# frog.net
KiCad netlist of a schematic drawn in EAGLE
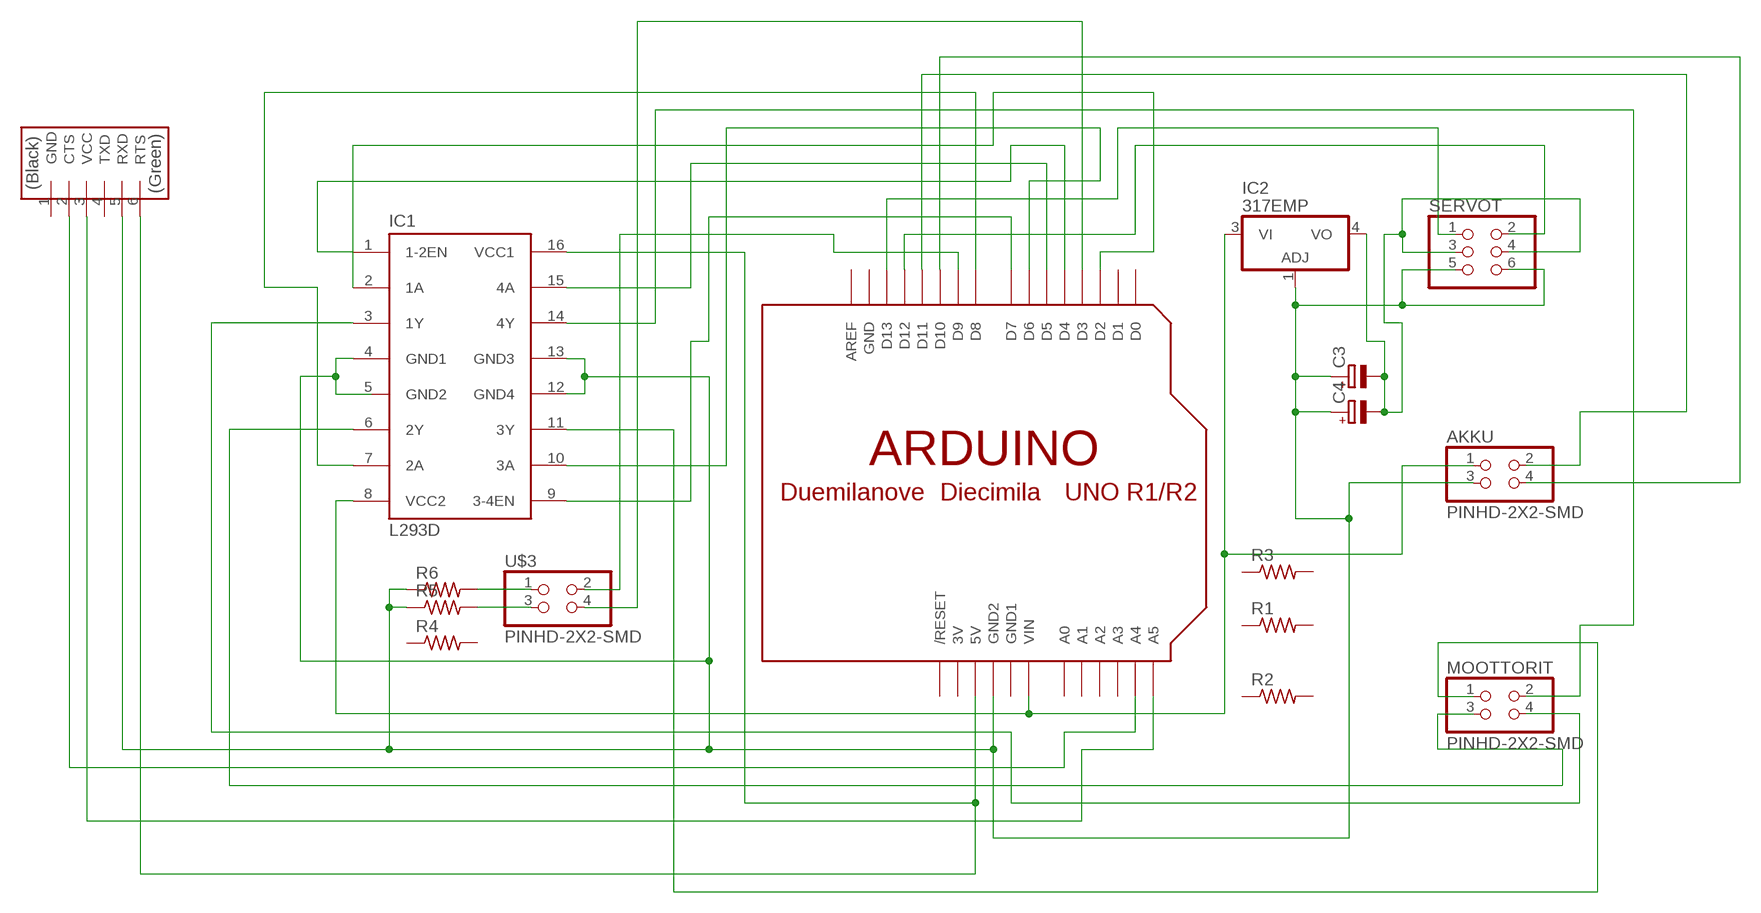
[diagram p0: schematic, sheet 1]

(export (version "E")
  (design (tool "Eeschema 10.0.6"))
  (components
    (comp (ref "AKKU")
      (value "PINHD-2X2-SMD")
      (footprint "eagle-import:2X02SMD")
      (libsource (lib "eagle-import") (part "PINHD-2X2-SMD"))
    )
    (comp (ref "C3")
      (value "CPOL-EUE/7260-38W")
      (footprint "eagle-import:E_7260-38W")
      (libsource (lib "eagle-import") (part "CPOL-EUE/7260-38W"))
    )
    (comp (ref "C4")
      (value "CPOL-EUE/7260-38W")
      (footprint "eagle-import:E_7260-38W")
      (libsource (lib "eagle-import") (part "CPOL-EUE/7260-38W"))
    )
    (comp (ref "IC1")
      (value "L293D")
      (footprint "eagle-import:DIL16")
      (libsource (lib "eagle-import") (part "L293D"))
    )
    (comp (ref "IC2")
      (value "317EMP")
      (footprint "eagle-import:SOT223")
      (libsource (lib "eagle-import") (part "317EMP"))
    )
    (comp (ref "MOOTTORIT")
      (value "PINHD-2X2-SMD")
      (footprint "eagle-import:2X02SMD")
      (libsource (lib "eagle-import") (part "PINHD-2X2-SMD"))
    )
    (comp (ref "R1")
      (value "RES-US1206FAB")
      (footprint "eagle-import:R1206FAB")
      (libsource (lib "eagle-import") (part "RES-US1206FAB"))
    )
    (comp (ref "R2")
      (value "RES-US1206FAB")
      (footprint "eagle-import:R1206FAB")
      (libsource (lib "eagle-import") (part "RES-US1206FAB"))
    )
    (comp (ref "R3")
      (value "RES-US1206FAB")
      (footprint "eagle-import:R1206FAB")
      (libsource (lib "eagle-import") (part "RES-US1206FAB"))
    )
    (comp (ref "R4")
      (value "RES-US1206FAB")
      (footprint "eagle-import:R1206FAB")
      (libsource (lib "eagle-import") (part "RES-US1206FAB"))
    )
    (comp (ref "R5")
      (value "RES-US1206FAB")
      (footprint "eagle-import:R1206FAB")
      (libsource (lib "eagle-import") (part "RES-US1206FAB"))
    )
    (comp (ref "R6")
      (value "RES-US1206FAB")
      (footprint "eagle-import:R1206FAB")
      (libsource (lib "eagle-import") (part "RES-US1206FAB"))
    )
    (comp (ref "SERVOT")
      (value "PINHD-2X3-SMD")
      (footprint "eagle-import:2X03SMD")
      (libsource (lib "eagle-import") (part "PINHD-2X3-SMD"))
    )
    (comp (ref "U$1")
      (value "ARDUINOUNO")
      (footprint "eagle-import:ARDUINO")
      (libsource (lib "eagle-import") (part "ARDUINOUNO"))
    )
    (comp (ref "U$2")
      (value "FTDI-SMD-HEADER")
      (footprint "eagle-import:1X06SMD")
      (libsource (lib "eagle-import") (part "FTDI-SMD-HEADER"))
    )
    (comp (ref "U$3")
      (value "PINHD-2X2-SMD")
      (footprint "eagle-import:2X02SMD")
      (libsource (lib "eagle-import") (part "PINHD-2X2-SMD"))
    )
  )
  (nets
    (net (code "1") (name "/3V") (class "Default")
      (node (ref "U$1") (pin "3V") (pinfunction "3V_3V") (pintype "power_in"))
    )
    (net (code "2") (name "/GND") (class "Default")
      (node (ref "U$1") (pin "GND") (pinfunction "GND_GND") (pintype "power_in"))
    )
    (net (code "3") (name "/GND1") (class "Default")
      (node (ref "U$1") (pin "GND1") (pinfunction "GND1_GND1") (pintype "power_in"))
    )
    (net (code "4") (name "/GND2") (class "Default")
      (node (ref "IC1") (pin "5") (pinfunction "GND2_5") (pintype "power_in"))
    )
    (net (code "5") (name "Net-(AKKU-Pad2)") (class "Default")
      (node (ref "AKKU") (pin "2") (pinfunction "2_2") (pintype "passive"))
      (node (ref "U$1") (pin "D11") (pinfunction "D11_D11") (pintype "bidirectional"))
    )
    (net (code "6") (name "Net-(AKKU-Pad4)") (class "Default")
      (node (ref "AKKU") (pin "4") (pinfunction "4_4") (pintype "passive"))
      (node (ref "U$1") (pin "D10") (pinfunction "D10_D10") (pintype "bidirectional"))
    )
    (net (code "7") (name "Net-(IC1-1-2EN)") (class "Default")
      (node (ref "IC1") (pin "1") (pinfunction "1-2EN_1") (pintype "input"))
      (node (ref "U$1") (pin "D4") (pinfunction "D4_D4") (pintype "bidirectional"))
    )
    (net (code "8") (name "Net-(IC1-1A)") (class "Default")
      (node (ref "IC1") (pin "2") (pinfunction "1A_2") (pintype "input"))
      (node (ref "U$1") (pin "D2") (pinfunction "D2_D2") (pintype "bidirectional"))
    )
    (net (code "9") (name "Net-(IC1-1Y)") (class "Default")
      (node (ref "IC1") (pin "3") (pinfunction "1Y_3") (pintype "output"))
      (node (ref "MOOTTORIT") (pin "4") (pinfunction "4_4") (pintype "passive"))
    )
    (net (code "10") (name "Net-(IC1-2A)") (class "Default")
      (node (ref "IC1") (pin "7") (pinfunction "2A_7") (pintype "input"))
      (node (ref "U$1") (pin "D8") (pinfunction "D8_D8") (pintype "bidirectional"))
    )
    (net (code "11") (name "Net-(IC1-2Y)") (class "Default")
      (node (ref "IC1") (pin "6") (pinfunction "2Y_6") (pintype "output"))
      (node (ref "MOOTTORIT") (pin "3") (pinfunction "3_3") (pintype "passive"))
    )
    (net (code "12") (name "Net-(IC1-3-4EN)") (class "Default")
      (node (ref "IC1") (pin "9") (pinfunction "3-4EN_9") (pintype "input"))
      (node (ref "U$1") (pin "D7") (pinfunction "D7_D7") (pintype "bidirectional"))
    )
    (net (code "13") (name "Net-(IC1-3A)") (class "Default")
      (node (ref "IC1") (pin "10") (pinfunction "3A_10") (pintype "input"))
      (node (ref "U$1") (pin "D6") (pinfunction "D6_D6") (pintype "bidirectional"))
    )
    (net (code "14") (name "Net-(IC1-3Y)") (class "Default")
      (node (ref "IC1") (pin "11") (pinfunction "3Y_11") (pintype "output"))
      (node (ref "MOOTTORIT") (pin "1") (pinfunction "1_1") (pintype "passive"))
    )
    (net (code "15") (name "Net-(IC1-4A)") (class "Default")
      (node (ref "IC1") (pin "15") (pinfunction "4A_15") (pintype "input"))
      (node (ref "U$1") (pin "D5") (pinfunction "D5_D5") (pintype "bidirectional"))
    )
    (net (code "16") (name "Net-(IC1-4Y)") (class "Default")
      (node (ref "IC1") (pin "14") (pinfunction "4Y_14") (pintype "output"))
      (node (ref "MOOTTORIT") (pin "2") (pinfunction "2_2") (pintype "passive"))
    )
    (net (code "17") (name "Net-(IC1-GND1)") (class "Default")
      (node (ref "AKKU") (pin "3") (pinfunction "3_3") (pintype "passive"))
      (node (ref "C3") (pin "+") (pinfunction "+_+") (pintype "passive"))
      (node (ref "C4") (pin "+") (pinfunction "+_+") (pintype "passive"))
      (node (ref "IC1") (pin "12") (pinfunction "GND4_12") (pintype "power_in"))
      (node (ref "IC1") (pin "13") (pinfunction "GND3_13") (pintype "power_in"))
      (node (ref "IC1") (pin "4") (pinfunction "GND1_4") (pintype "power_in"))
      (node (ref "IC2") (pin "1") (pinfunction "ADJ_1") (pintype "input"))
      (node (ref "R5") (pin "1") (pinfunction "1_1") (pintype "passive"))
      (node (ref "R6") (pin "1") (pinfunction "1_1") (pintype "passive"))
      (node (ref "SERVOT") (pin "5") (pinfunction "5_5") (pintype "passive"))
      (node (ref "SERVOT") (pin "6") (pinfunction "6_6") (pintype "passive"))
      (node (ref "U$1") (pin "GND2") (pinfunction "GND2_GND2") (pintype "power_in"))
      (node (ref "U$2") (pin "5") (pinfunction "RXD_5") (pintype "bidirectional"))
    )
    (net (code "18") (name "Net-(IC1-VCC1)") (class "Default")
      (node (ref "IC1") (pin "16") (pinfunction "VCC1_16") (pintype "power_in"))
      (node (ref "U$1") (pin "5V") (pinfunction "5V_5V") (pintype "power_in"))
      (node (ref "U$2") (pin "6") (pinfunction "RTS_6") (pintype "bidirectional"))
    )
    (net (code "19") (name "Net-(IC1-VCC2)") (class "Default")
      (node (ref "AKKU") (pin "1") (pinfunction "1_1") (pintype "passive"))
      (node (ref "IC1") (pin "8") (pinfunction "VCC2_8") (pintype "power_in"))
      (node (ref "IC2") (pin "3") (pinfunction "VI_3") (pintype "input"))
      (node (ref "U$1") (pin "VIN") (pinfunction "VIN_VIN") (pintype "power_in"))
    )
    (net (code "20") (name "Net-(IC2-VO)") (class "Default")
      (node (ref "C3") (pin "-") (pinfunction "-_-") (pintype "passive"))
      (node (ref "C4") (pin "-") (pinfunction "-_-") (pintype "passive"))
      (node (ref "IC2") (pin "4") (pinfunction "VO_4") (pintype "passive"))
      (node (ref "SERVOT") (pin "3") (pinfunction "3_3") (pintype "passive"))
      (node (ref "SERVOT") (pin "4") (pinfunction "4_4") (pintype "passive"))
    )
    (net (code "21") (name "Net-(R5-Pad2)") (class "Default")
      (node (ref "R5") (pin "2") (pinfunction "2_2") (pintype "passive"))
      (node (ref "U$3") (pin "3") (pinfunction "3_3") (pintype "passive"))
    )
    (net (code "22") (name "Net-(R6-Pad2)") (class "Default")
      (node (ref "R6") (pin "2") (pinfunction "2_2") (pintype "passive"))
      (node (ref "U$3") (pin "1") (pinfunction "1_1") (pintype "passive"))
    )
    (net (code "23") (name "Net-(SERVOT-Pad1)") (class "Default")
      (node (ref "SERVOT") (pin "1") (pinfunction "1_1") (pintype "passive"))
      (node (ref "U$1") (pin "D13") (pinfunction "D13_D13") (pintype "bidirectional"))
    )
    (net (code "24") (name "Net-(SERVOT-Pad2)") (class "Default")
      (node (ref "SERVOT") (pin "2") (pinfunction "2_2") (pintype "passive"))
      (node (ref "U$1") (pin "D12") (pinfunction "D12_D12") (pintype "bidirectional"))
    )
    (net (code "25") (name "Net-(U$1-PadD3)") (class "Default")
      (node (ref "U$1") (pin "D3") (pinfunction "D3_D3") (pintype "bidirectional"))
      (node (ref "U$3") (pin "4") (pinfunction "4_4") (pintype "passive"))
    )
    (net (code "26") (name "Net-(U$1-PadD9)") (class "Default")
      (node (ref "U$1") (pin "D9") (pinfunction "D9_D9") (pintype "bidirectional"))
      (node (ref "U$3") (pin "2") (pinfunction "2_2") (pintype "passive"))
    )
    (net (code "27") (name "Net-(U$2-CTS)") (class "Default")
      (node (ref "U$1") (pin "A4") (pinfunction "A4_A4") (pintype "bidirectional"))
      (node (ref "U$2") (pin "2") (pinfunction "CTS_2") (pintype "bidirectional"))
    )
    (net (code "28") (name "Net-(U$2-VCC)") (class "Default")
      (node (ref "U$1") (pin "A5") (pinfunction "A5_A5") (pintype "bidirectional"))
      (node (ref "U$2") (pin "3") (pinfunction "VCC_3") (pintype "bidirectional"))
    )
    (net (code "29") (name "unconnected-(R1-Pad1)") (class "Default")
      (node (ref "R1") (pin "1") (pinfunction "1_1") (pintype "passive"))
    )
    (net (code "30") (name "unconnected-(R1-Pad2)") (class "Default")
      (node (ref "R1") (pin "2") (pinfunction "2_2") (pintype "passive"))
    )
    (net (code "31") (name "unconnected-(R2-Pad1)") (class "Default")
      (node (ref "R2") (pin "1") (pinfunction "1_1") (pintype "passive"))
    )
    (net (code "32") (name "unconnected-(R2-Pad2)") (class "Default")
      (node (ref "R2") (pin "2") (pinfunction "2_2") (pintype "passive"))
    )
    (net (code "33") (name "unconnected-(R3-Pad1)") (class "Default")
      (node (ref "R3") (pin "1") (pinfunction "1_1") (pintype "passive"))
    )
    (net (code "34") (name "unconnected-(R3-Pad2)") (class "Default")
      (node (ref "R3") (pin "2") (pinfunction "2_2") (pintype "passive"))
    )
    (net (code "35") (name "unconnected-(R4-Pad1)") (class "Default")
      (node (ref "R4") (pin "1") (pinfunction "1_1") (pintype "passive"))
    )
    (net (code "36") (name "unconnected-(R4-Pad2)") (class "Default")
      (node (ref "R4") (pin "2") (pinfunction "2_2") (pintype "passive"))
    )
    (net (code "37") (name "unconnected-(U$1-PadA0)") (class "Default")
      (node (ref "U$1") (pin "A0") (pinfunction "A0_A0") (pintype "bidirectional"))
    )
    (net (code "38") (name "unconnected-(U$1-PadA1)") (class "Default")
      (node (ref "U$1") (pin "A1") (pinfunction "A1_A1") (pintype "bidirectional"))
    )
    (net (code "39") (name "unconnected-(U$1-PadA2)") (class "Default")
      (node (ref "U$1") (pin "A2") (pinfunction "A2_A2") (pintype "bidirectional"))
    )
    (net (code "40") (name "unconnected-(U$1-PadA3)") (class "Default")
      (node (ref "U$1") (pin "A3") (pinfunction "A3_A3") (pintype "bidirectional"))
    )
    (net (code "41") (name "unconnected-(U$1-PadAREF)") (class "Default")
      (node (ref "U$1") (pin "AREF") (pinfunction "AREF_AREF") (pintype "bidirectional"))
    )
    (net (code "42") (name "unconnected-(U$1-PadD0)") (class "Default")
      (node (ref "U$1") (pin "D0") (pinfunction "D0_D0") (pintype "bidirectional"))
    )
    (net (code "43") (name "unconnected-(U$1-PadD1)") (class "Default")
      (node (ref "U$1") (pin "D1") (pinfunction "D1_D1") (pintype "bidirectional"))
    )
    (net (code "44") (name "unconnected-(U$1-{slash}RESET-PadRESET)") (class "Default")
      (node (ref "U$1") (pin "RESET") (pinfunction "/RESET_RESET") (pintype "bidirectional"))
    )
    (net (code "45") (name "unconnected-(U$2-GND-Pad1)") (class "Default")
      (node (ref "U$2") (pin "1") (pinfunction "GND_1") (pintype "bidirectional"))
    )
    (net (code "46") (name "unconnected-(U$2-TXD-Pad4)") (class "Default")
      (node (ref "U$2") (pin "4") (pinfunction "TXD_4") (pintype "bidirectional"))
    )
  )
)
